# DD2.net
KiCad netlist of a schematic drawn in Altium Designer
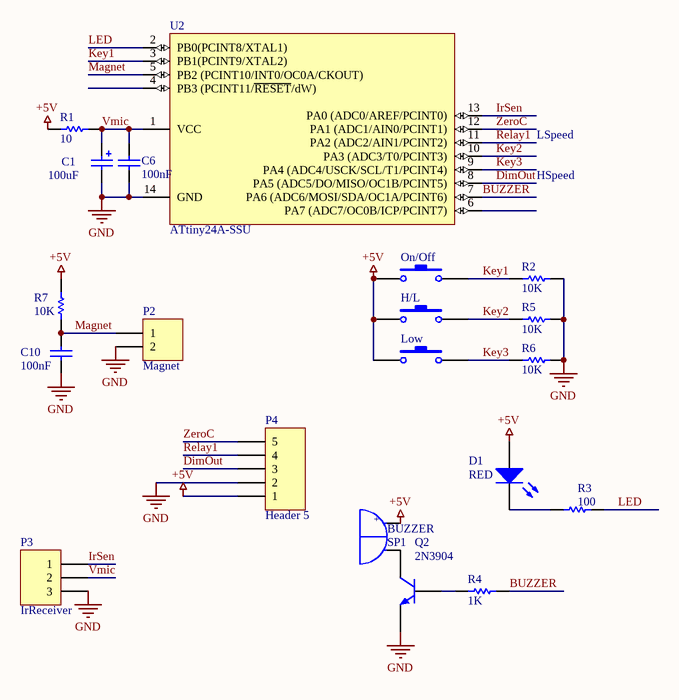
[diagram p0: DD2.SchDoc]

(export (version "E")
  (design (tool "Eeschema 10.0.6"))
  (components
    (comp (ref "C1")
      (value "100uF")
      (footprint "RB.15/.2")
      (description "Polarized Capacitor")
      (fields (field (name "PUBLISHER") "Altium Limited"))
      (libsource (lib "MySchLib") (part "Cap Pol"))
    )
    (comp (ref "C6")
      (value "100nF")
      (footprint "RAD0.2")
      (description "Capacitor")
      (fields (field (name "PUBLISHER") "Altium Limited"))
      (libsource (lib "MySchLib") (part "Cap"))
    )
    (comp (ref "C10")
      (value "100nF")
      (footprint "RAD0.2")
      (description "Capacitor SMD")
      (fields (field (name "PUBLISHER") "Altium Limited"))
      (libsource (lib "MySchLib") (part "Cap"))
    )
    (comp (ref "D1")
      (value "RED")
      (footprint "LED0.5")
      (description "LED Radial 0.5")
      (fields (field (name "PUBLISHER") "Altium Limited"))
      (libsource (lib "MySchLib") (part "LED0.5"))
    )
    (comp (ref "P2")
      (value "Magnet")
      (footprint "Magnet")
      (description "Header, 2-Pin")
      (fields (field (name "PUBLISHER") "Altium Limited"))
      (libsource (lib "Miscellaneous Connectors") (part "Header 2"))
    )
    (comp (ref "P3")
      (value "IrReceiver")
      (footprint "IrRec1")
      (description "3pin")
      (fields (field (name "PUBLISHER") "Altium Limited"))
      (libsource (lib "Miscellaneous Connectors") (part "Header 3"))
    )
    (comp (ref "P4")
      (value "Header 5")
      (footprint "xH5RA")
      (description "Header, 5-Pin")
      (fields (field (name "PUBLISHER") "Altium Limited"))
      (libsource (lib "Miscellaneous Connectors") (part "Header 5"))
    )
    (comp (ref "Q2")
      (value "2N3904")
      (footprint "TO92BS2")
      (description "NPN General Purpose Amplifier")
      (fields (field (name "PUBLISHER") "Altium Limited"))
      (libsource (lib "MySchLib") (part "BC337"))
    )
    (comp (ref "R1")
      (value "10")
      (footprint "RES0.35")
      (description "Resistor")
      (fields (field (name "PUBLISHER") "Altium Limited"))
      (libsource (lib "MySchLib") (part "Resistor"))
    )
    (comp (ref "R2")
      (value "10K")
      (footprint "RES0.35")
      (description "Resistor")
      (fields (field (name "PUBLISHER") "Altium Limited"))
      (libsource (lib "MySchLib") (part "Resistor"))
    )
    (comp (ref "R3")
      (value "100")
      (footprint "RES0.35")
      (description "Resistor")
      (fields (field (name "PUBLISHER") "Altium Limited"))
      (libsource (lib "MySchLib") (part "Resistor"))
    )
    (comp (ref "R4")
      (value "1K")
      (footprint "RES0.35")
      (description "Resistor")
      (fields (field (name "PUBLISHER") "Altium Limited"))
      (libsource (lib "") (part "Resistor_1"))
    )
    (comp (ref "R5")
      (value "10K")
      (footprint "RES0.35")
      (description "Resistor")
      (fields (field (name "PUBLISHER") "Altium Limited"))
      (libsource (lib "MySchLib") (part "Resistor"))
    )
    (comp (ref "R6")
      (value "10K")
      (footprint "RES0.35")
      (description "Resistor")
      (fields (field (name "PUBLISHER") "Altium Limited"))
      (libsource (lib "MySchLib") (part "Resistor"))
    )
    (comp (ref "R7")
      (value "10K")
      (footprint "RES0.35")
      (description "Resistor")
      (fields (field (name "PUBLISHER") "Altium Limited"))
      (libsource (lib "MySchLib") (part "Resistor"))
    )
    (comp (ref "S1")
      (value "On/Off")
      (footprint "PUSHBOT2")
      (description "6x6x7")
      (fields (field (name "PUBLISHER") "Altium Limited"))
      (libsource (lib "MySchLib") (part "SW-PB"))
    )
    (comp (ref "S2")
      (value "H/L")
      (footprint "PUSHBOT2")
      (description "6x6x7")
      (fields (field (name "PUBLISHER") "Altium Limited"))
      (libsource (lib "MySchLib") (part "SW-PB"))
    )
    (comp (ref "S3")
      (value "Low")
      (footprint "PUSHBOT2")
      (description "6x6x7")
      (fields (field (name "PUBLISHER") "Altium Limited"))
      (libsource (lib "MySchLib") (part "SW-PB"))
    )
    (comp (ref "SP1")
      (value "BUZZER")
      (footprint "RB.3/.6")
      (description "5Volt")
      (libsource (lib "MySchLib") (part "BUZZER"))
    )
    (comp (ref "U2")
      (value "ATtiny24A-SSU")
      (footprint "SOIC14")
      (description "8-Bit AVR Microcontroller with 2K Bytes of Flash Memory")
      (fields (field (name "PUBLISHER") "Altium Limited"))
      (libsource (lib "MySchLib") (part "ATtiny24-16PC"))
    )
  )
  (nets
    (net (code "1") (name "+5V") (class "Default")
      (node (ref "D1") (pin "1") (pinfunction "A_1") (pintype "passive"))
      (node (ref "P4") (pin "1") (pinfunction "1_1") (pintype "passive"))
      (node (ref "R1") (pin "2") (pinfunction "2_2") (pintype "passive"))
      (node (ref "R7") (pin "2") (pinfunction "2_2") (pintype "passive"))
      (node (ref "S1") (pin "1") (pinfunction "1_1") (pintype "passive"))
      (node (ref "S2") (pin "1") (pinfunction "1_1") (pintype "passive"))
      (node (ref "S3") (pin "1") (pinfunction "1_1") (pintype "passive"))
      (node (ref "SP1") (pin "1") (pinfunction "1_1") (pintype "passive"))
    )
    (net (code "2") (name "/BUZZER") (class "Default")
      (node (ref "R4") (pin "1") (pinfunction "1_1") (pintype "passive"))
      (node (ref "U2") (pin "7") (pinfunction "PA6_(ADC6/MOSI/SDA/OC1A/PCINT6)_7") (pintype "bidirectional"))
    )
    (net (code "3") (name "/DimOut") (class "Default")
      (node (ref "P4") (pin "3") (pinfunction "3_3") (pintype "passive"))
      (node (ref "U2") (pin "8") (pinfunction "PA5_(ADC5/DO/MISO/OC1B/PCINT5)_8") (pintype "bidirectional"))
    )
    (net (code "4") (name "/IrSen") (class "Default")
      (node (ref "P3") (pin "1") (pinfunction "1_1") (pintype "passive"))
      (node (ref "U2") (pin "13") (pinfunction "PA0_(ADC0/AREF/PCINT0)_13") (pintype "bidirectional"))
    )
    (net (code "5") (name "/Key1") (class "Default")
      (node (ref "R2") (pin "2") (pinfunction "2_2") (pintype "passive"))
      (node (ref "S1") (pin "2") (pinfunction "2_2") (pintype "passive"))
      (node (ref "U2") (pin "3") (pinfunction "PB1(PCINT9/XTAL2)_3") (pintype "bidirectional"))
    )
    (net (code "6") (name "/Key2") (class "Default")
      (node (ref "R5") (pin "2") (pinfunction "2_2") (pintype "passive"))
      (node (ref "S2") (pin "2") (pinfunction "2_2") (pintype "passive"))
      (node (ref "U2") (pin "10") (pinfunction "PA3_(ADC3/T0/PCINT3)_10") (pintype "bidirectional"))
    )
    (net (code "7") (name "/Key3") (class "Default")
      (node (ref "R6") (pin "2") (pinfunction "2_2") (pintype "passive"))
      (node (ref "S3") (pin "2") (pinfunction "2_2") (pintype "passive"))
      (node (ref "U2") (pin "9") (pinfunction "PA4_(ADC4/USCK/SCL/T1/PCINT4)_9") (pintype "bidirectional"))
    )
    (net (code "8") (name "/LED") (class "Default")
      (node (ref "R3") (pin "1") (pinfunction "1_1") (pintype "passive"))
      (node (ref "U2") (pin "2") (pinfunction "PB0(PCINT8/XTAL1)_2") (pintype "bidirectional"))
    )
    (net (code "9") (name "/Magnet") (class "Default")
      (node (ref "C10") (pin "2") (pinfunction "2_2") (pintype "passive"))
      (node (ref "P2") (pin "1") (pinfunction "1_1") (pintype "passive"))
      (node (ref "R7") (pin "1") (pinfunction "1_1") (pintype "passive"))
      (node (ref "U2") (pin "5") (pinfunction "PB2_(PCINT10/INT0/OC0A/CKOUT)_5") (pintype "bidirectional"))
    )
    (net (code "10") (name "/Relay1") (class "Default")
      (node (ref "P4") (pin "4") (pinfunction "4_4") (pintype "passive"))
      (node (ref "U2") (pin "11") (pinfunction "PA2_(ADC2/AIN1/PCINT2)_11") (pintype "bidirectional"))
    )
    (net (code "11") (name "/Vmic") (class "Default")
      (node (ref "C1") (pin "1") (pinfunction "1_1") (pintype "passive"))
      (node (ref "C6") (pin "2") (pinfunction "2_2") (pintype "passive"))
      (node (ref "P3") (pin "2") (pinfunction "2_2") (pintype "passive"))
      (node (ref "R1") (pin "1") (pinfunction "1_1") (pintype "passive"))
      (node (ref "U2") (pin "1") (pinfunction "VCC_1") (pintype "power_in"))
    )
    (net (code "12") (name "/ZeroC") (class "Default")
      (node (ref "P4") (pin "5") (pinfunction "5_5") (pintype "passive"))
      (node (ref "U2") (pin "12") (pinfunction "PA1_(ADC1/AIN0/PCINT1)_12") (pintype "bidirectional"))
    )
    (net (code "13") (name "GND") (class "Default")
      (node (ref "C1") (pin "2") (pinfunction "2_2") (pintype "passive"))
      (node (ref "C10") (pin "1") (pinfunction "1_1") (pintype "passive"))
      (node (ref "C6") (pin "1") (pinfunction "1_1") (pintype "passive"))
      (node (ref "P2") (pin "2") (pinfunction "2_2") (pintype "passive"))
      (node (ref "P3") (pin "3") (pinfunction "3_3") (pintype "passive"))
      (node (ref "P4") (pin "2") (pinfunction "2_2") (pintype "passive"))
      (node (ref "Q2") (pin "3") (pinfunction "E_3") (pintype "passive"))
      (node (ref "R2") (pin "1") (pinfunction "1_1") (pintype "passive"))
      (node (ref "R5") (pin "1") (pinfunction "1_1") (pintype "passive"))
      (node (ref "R6") (pin "1") (pinfunction "1_1") (pintype "passive"))
      (node (ref "U2") (pin "14") (pinfunction "GND_14") (pintype "power_in"))
    )
    (net (code "14") (name "Net-(D1-K)") (class "Default")
      (node (ref "D1") (pin "2") (pinfunction "K_2") (pintype "passive"))
      (node (ref "R3") (pin "2") (pinfunction "2_2") (pintype "passive"))
    )
    (net (code "15") (name "Net-(Q2-B)") (class "Default")
      (node (ref "Q2") (pin "1") (pinfunction "B_1") (pintype "passive"))
      (node (ref "R4") (pin "2") (pinfunction "2_2") (pintype "passive"))
    )
    (net (code "16") (name "Net-(Q2-C)") (class "Default")
      (node (ref "Q2") (pin "2") (pinfunction "C_2") (pintype "passive"))
      (node (ref "SP1") (pin "2") (pinfunction "2_2") (pintype "passive"))
    )
    (net (code "17") (name "unconnected-(U2-PA7_(ADC7{slash}OC0B{slash}ICP{slash}PCINT7)-Pad6)") (class "Default")
      (node (ref "U2") (pin "6") (pinfunction "PA7_(ADC7/OC0B/ICP/PCINT7)_6") (pintype "bidirectional"))
    )
    (net (code "18") (name "unconnected-(U2-PB3_(PCINT11{slash}~{RESET}{slash}dW)-Pad4)") (class "Default")
      (node (ref "U2") (pin "4") (pinfunction "PB3_(PCINT11/~{RESET}/dW)_4") (pintype "bidirectional"))
    )
  )
)
